# power_board.net
KiCad netlist of a schematic drawn in EAGLE
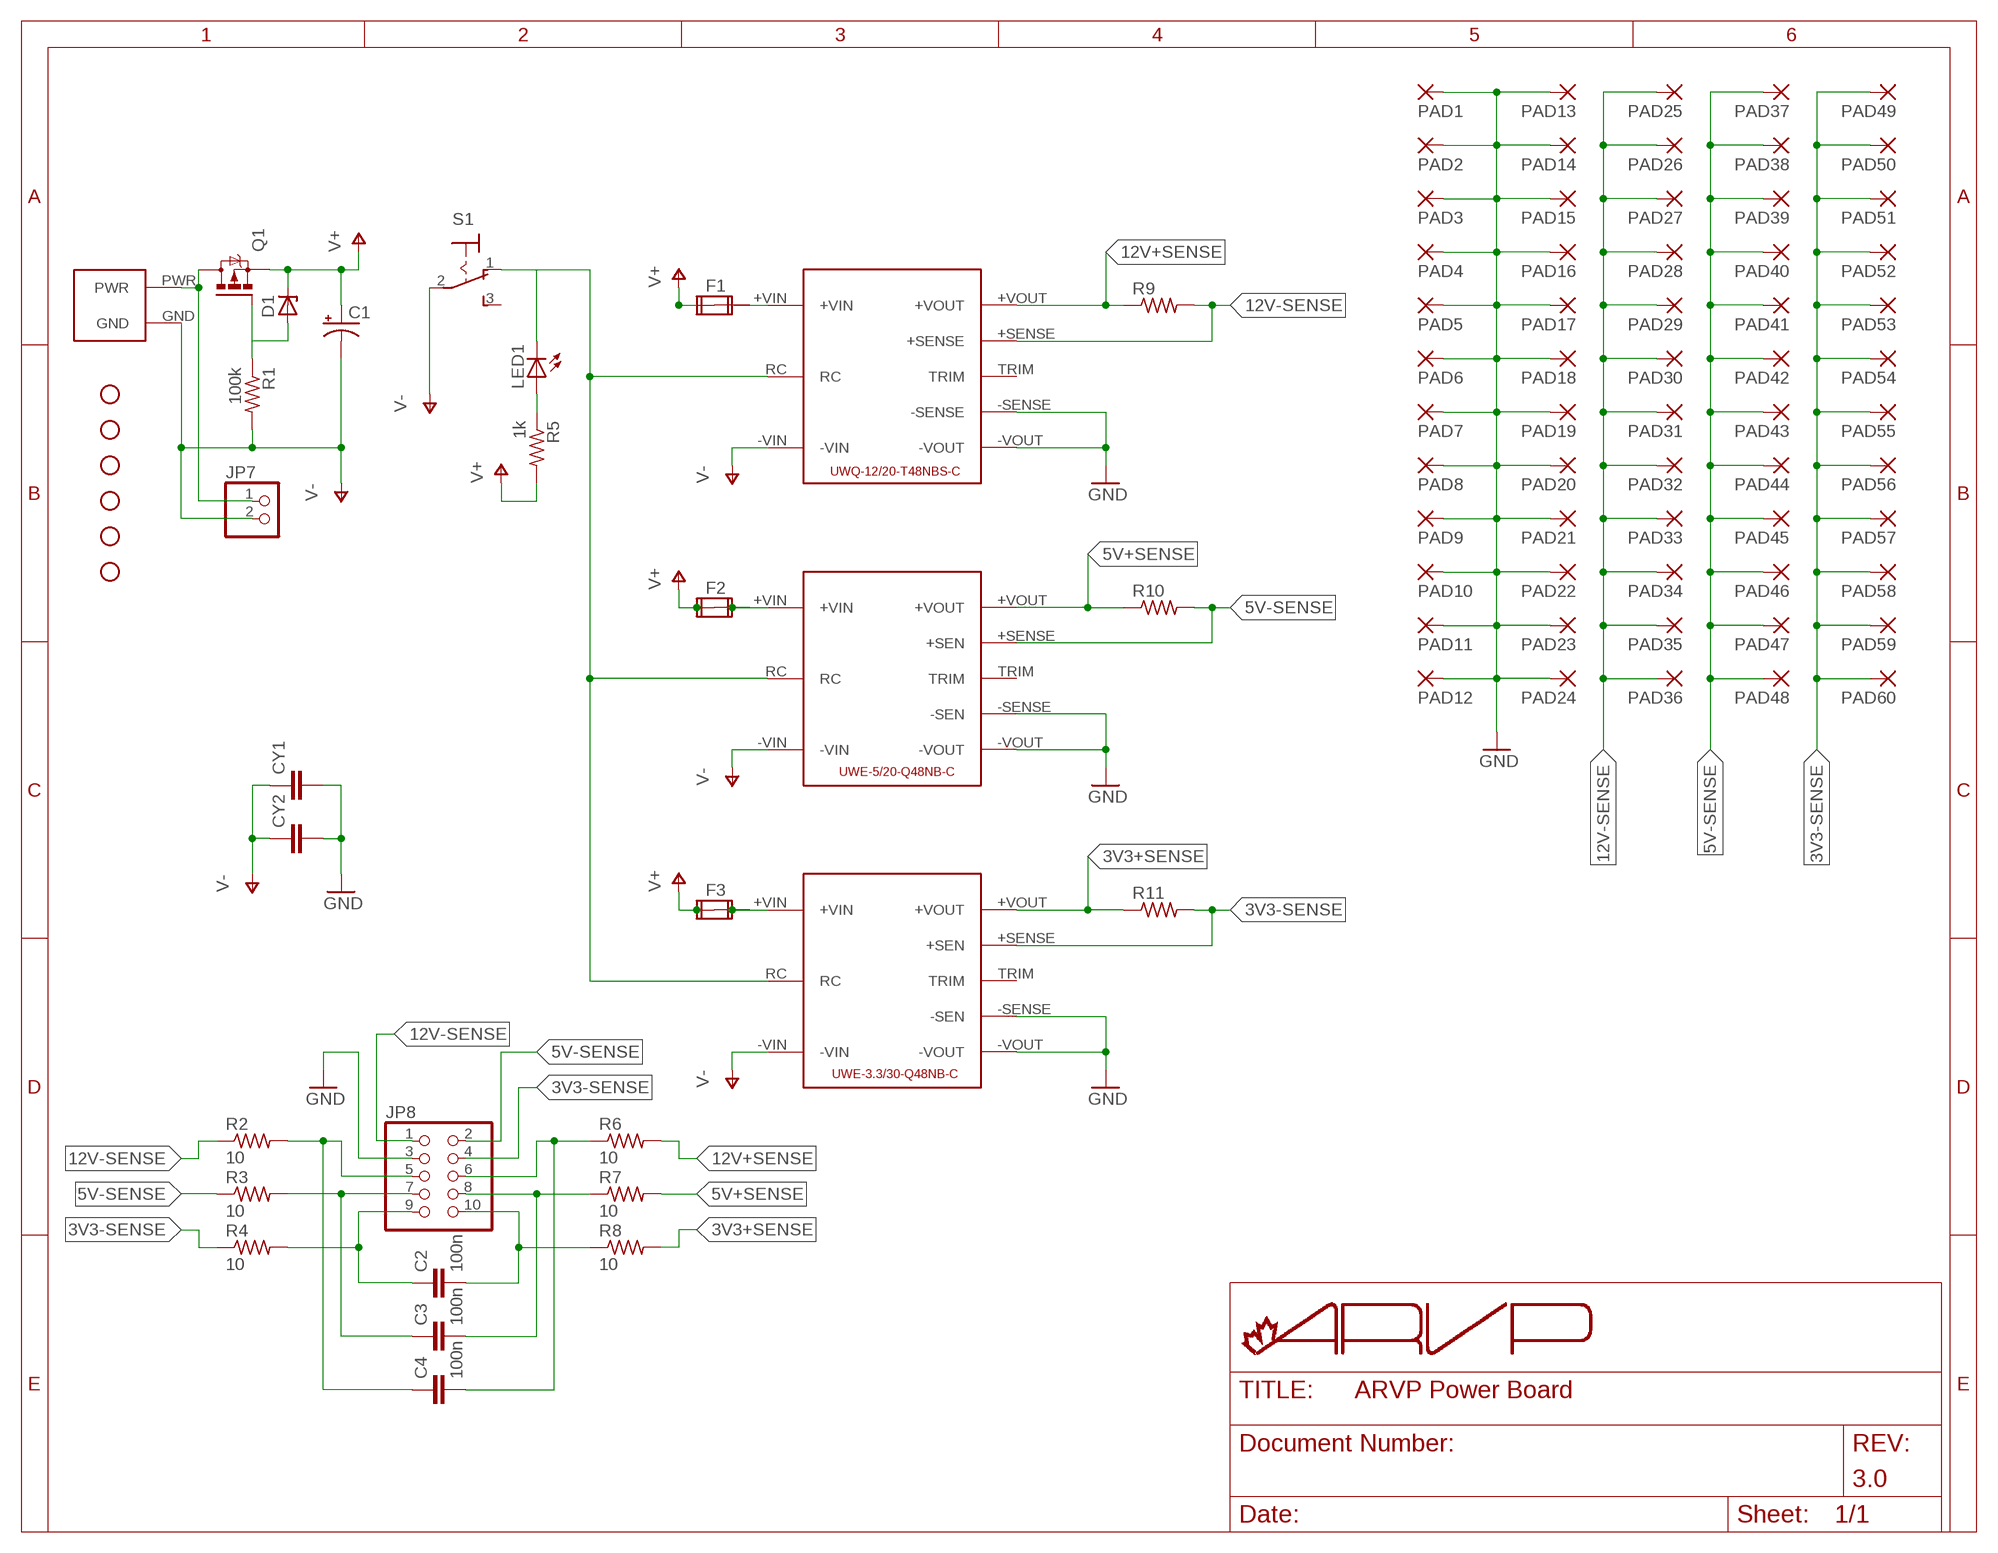
[diagram p0: schematic, sheet 1]

(export (version "E")
  (design (tool "Eeschema 10.0.6"))
  (components
    (comp (ref "C1")
      (value "CPOL-USE5-10.5")
      (footprint "eagle-import:E5-10,5")
      (libsource (lib "eagle-import") (part "CPOL-USE5-10.5"))
    )
    (comp (ref "C2")
      (value "100n")
      (footprint "eagle-import:C025-024X044")
      (libsource (lib "eagle-import") (part "C-EU025-024X044"))
    )
    (comp (ref "C3")
      (value "100n")
      (footprint "eagle-import:C025-024X044")
      (libsource (lib "eagle-import") (part "C-EU025-024X044"))
    )
    (comp (ref "C4")
      (value "100n")
      (footprint "eagle-import:C025-024X044")
      (libsource (lib "eagle-import") (part "C-EU025-024X044"))
    )
    (comp (ref "CY1")
      (value "CYYC7B5")
      (footprint "eagle-import:YC7B5")
      (libsource (lib "eagle-import") (part "CYYC7B5"))
    )
    (comp (ref "CY2")
      (value "CYYC7B5")
      (footprint "eagle-import:YC7B5")
      (libsource (lib "eagle-import") (part "CYYC7B5"))
    )
    (comp (ref "D1")
      (value "ZENER-DIODEDO35Z10")
      (footprint "eagle-import:DO35Z10")
      (libsource (lib "eagle-import") (part "ZENER-DIODEDO35Z10"))
    )
    (comp (ref "F1")
      (value "FUSE2P")
      (footprint "eagle-import:FUSE1")
      (libsource (lib "eagle-import") (part "FUSE2P"))
    )
    (comp (ref "F2")
      (value "FUSE2P")
      (footprint "eagle-import:FUSE1")
      (libsource (lib "eagle-import") (part "FUSE2P"))
    )
    (comp (ref "F3")
      (value "FUSE2P")
      (footprint "eagle-import:FUSE1")
      (libsource (lib "eagle-import") (part "FUSE2P"))
    )
    (comp (ref "JP1")
      (value "STAND-OFF")
      (footprint "eagle-import:STAND-OFF")
      (libsource (lib "eagle-import") (part "STAND-OFF"))
    )
    (comp (ref "JP2")
      (value "STAND-OFF")
      (footprint "eagle-import:STAND-OFF")
      (libsource (lib "eagle-import") (part "STAND-OFF"))
    )
    (comp (ref "JP3")
      (value "STAND-OFF")
      (footprint "eagle-import:STAND-OFF")
      (libsource (lib "eagle-import") (part "STAND-OFF"))
    )
    (comp (ref "JP4")
      (value "STAND-OFF")
      (footprint "eagle-import:STAND-OFF")
      (libsource (lib "eagle-import") (part "STAND-OFF"))
    )
    (comp (ref "JP5")
      (value "STAND-OFF")
      (footprint "eagle-import:STAND-OFF")
      (libsource (lib "eagle-import") (part "STAND-OFF"))
    )
    (comp (ref "JP6")
      (value "STAND-OFF")
      (footprint "eagle-import:STAND-OFF")
      (libsource (lib "eagle-import") (part "STAND-OFF"))
    )
    (comp (ref "JP7")
      (value "PINHD-1X2")
      (footprint "eagle-import:1X02")
      (libsource (lib "eagle-import") (part "PINHD-1X2"))
    )
    (comp (ref "JP8")
      (value "PINHD-2X5")
      (footprint "eagle-import:2X05")
      (libsource (lib "eagle-import") (part "PINHD-2X5"))
    )
    (comp (ref "LED1")
      (value "LED3MM")
      (footprint "eagle-import:LED3MM")
      (libsource (lib "eagle-import") (part "LED3MM"))
    )
    (comp (ref "P$1")
      (value "AND_PWR")
      (footprint "eagle-import:AND_PWR")
      (libsource (lib "eagle-import") (part "AND_PWR"))
    )
    (comp (ref "PAD1")
      (value "2,15/1,0")
      (footprint "eagle-import:2,15_1,0")
      (libsource (lib "eagle-import") (part "2,15/1,0"))
    )
    (comp (ref "PAD2")
      (value "2,15/1,0")
      (footprint "eagle-import:2,15_1,0")
      (libsource (lib "eagle-import") (part "2,15/1,0"))
    )
    (comp (ref "PAD3")
      (value "2,15/1,0")
      (footprint "eagle-import:2,15_1,0")
      (libsource (lib "eagle-import") (part "2,15/1,0"))
    )
    (comp (ref "PAD4")
      (value "2,15/1,0")
      (footprint "eagle-import:2,15_1,0")
      (libsource (lib "eagle-import") (part "2,15/1,0"))
    )
    (comp (ref "PAD5")
      (value "2,15/1,0")
      (footprint "eagle-import:2,15_1,0")
      (libsource (lib "eagle-import") (part "2,15/1,0"))
    )
    (comp (ref "PAD6")
      (value "2,15/1,0")
      (footprint "eagle-import:2,15_1,0")
      (libsource (lib "eagle-import") (part "2,15/1,0"))
    )
    (comp (ref "PAD7")
      (value "2,15/1,0")
      (footprint "eagle-import:2,15_1,0")
      (libsource (lib "eagle-import") (part "2,15/1,0"))
    )
    (comp (ref "PAD8")
      (value "2,15/1,0")
      (footprint "eagle-import:2,15_1,0")
      (libsource (lib "eagle-import") (part "2,15/1,0"))
    )
    (comp (ref "PAD9")
      (value "2,15/1,0")
      (footprint "eagle-import:2,15_1,0")
      (libsource (lib "eagle-import") (part "2,15/1,0"))
    )
    (comp (ref "PAD10")
      (value "2,15/1,0")
      (footprint "eagle-import:2,15_1,0")
      (libsource (lib "eagle-import") (part "2,15/1,0"))
    )
    (comp (ref "PAD11")
      (value "2,15/1,0")
      (footprint "eagle-import:2,15_1,0")
      (libsource (lib "eagle-import") (part "2,15/1,0"))
    )
    (comp (ref "PAD12")
      (value "2,15/1,0")
      (footprint "eagle-import:2,15_1,0")
      (libsource (lib "eagle-import") (part "2,15/1,0"))
    )
    (comp (ref "PAD13")
      (value "2,15/1,0")
      (footprint "eagle-import:2,15_1,0")
      (libsource (lib "eagle-import") (part "2,15/1,0"))
    )
    (comp (ref "PAD14")
      (value "2,15/1,0")
      (footprint "eagle-import:2,15_1,0")
      (libsource (lib "eagle-import") (part "2,15/1,0"))
    )
    (comp (ref "PAD15")
      (value "2,15/1,0")
      (footprint "eagle-import:2,15_1,0")
      (libsource (lib "eagle-import") (part "2,15/1,0"))
    )
    (comp (ref "PAD16")
      (value "2,15/1,0")
      (footprint "eagle-import:2,15_1,0")
      (libsource (lib "eagle-import") (part "2,15/1,0"))
    )
    (comp (ref "PAD17")
      (value "2,15/1,0")
      (footprint "eagle-import:2,15_1,0")
      (libsource (lib "eagle-import") (part "2,15/1,0"))
    )
    (comp (ref "PAD18")
      (value "2,15/1,0")
      (footprint "eagle-import:2,15_1,0")
      (libsource (lib "eagle-import") (part "2,15/1,0"))
    )
    (comp (ref "PAD19")
      (value "2,15/1,0")
      (footprint "eagle-import:2,15_1,0")
      (libsource (lib "eagle-import") (part "2,15/1,0"))
    )
    (comp (ref "PAD20")
      (value "2,15/1,0")
      (footprint "eagle-import:2,15_1,0")
      (libsource (lib "eagle-import") (part "2,15/1,0"))
    )
    (comp (ref "PAD21")
      (value "2,15/1,0")
      (footprint "eagle-import:2,15_1,0")
      (libsource (lib "eagle-import") (part "2,15/1,0"))
    )
    (comp (ref "PAD22")
      (value "2,15/1,0")
      (footprint "eagle-import:2,15_1,0")
      (libsource (lib "eagle-import") (part "2,15/1,0"))
    )
    (comp (ref "PAD23")
      (value "2,15/1,0")
      (footprint "eagle-import:2,15_1,0")
      (libsource (lib "eagle-import") (part "2,15/1,0"))
    )
    (comp (ref "PAD24")
      (value "2,15/1,0")
      (footprint "eagle-import:2,15_1,0")
      (libsource (lib "eagle-import") (part "2,15/1,0"))
    )
    (comp (ref "PAD25")
      (value "2,15/1,0")
      (footprint "eagle-import:2,15_1,0")
      (libsource (lib "eagle-import") (part "2,15/1,0"))
    )
    (comp (ref "PAD26")
      (value "2,15/1,0")
      (footprint "eagle-import:2,15_1,0")
      (libsource (lib "eagle-import") (part "2,15/1,0"))
    )
    (comp (ref "PAD27")
      (value "2,15/1,0")
      (footprint "eagle-import:2,15_1,0")
      (libsource (lib "eagle-import") (part "2,15/1,0"))
    )
    (comp (ref "PAD28")
      (value "2,15/1,0")
      (footprint "eagle-import:2,15_1,0")
      (libsource (lib "eagle-import") (part "2,15/1,0"))
    )
    (comp (ref "PAD29")
      (value "2,15/1,0")
      (footprint "eagle-import:2,15_1,0")
      (libsource (lib "eagle-import") (part "2,15/1,0"))
    )
    (comp (ref "PAD30")
      (value "2,15/1,0")
      (footprint "eagle-import:2,15_1,0")
      (libsource (lib "eagle-import") (part "2,15/1,0"))
    )
    (comp (ref "PAD31")
      (value "2,15/1,0")
      (footprint "eagle-import:2,15_1,0")
      (libsource (lib "eagle-import") (part "2,15/1,0"))
    )
    (comp (ref "PAD32")
      (value "2,15/1,0")
      (footprint "eagle-import:2,15_1,0")
      (libsource (lib "eagle-import") (part "2,15/1,0"))
    )
    (comp (ref "PAD33")
      (value "2,15/1,0")
      (footprint "eagle-import:2,15_1,0")
      (libsource (lib "eagle-import") (part "2,15/1,0"))
    )
    (comp (ref "PAD34")
      (value "2,15/1,0")
      (footprint "eagle-import:2,15_1,0")
      (libsource (lib "eagle-import") (part "2,15/1,0"))
    )
    (comp (ref "PAD35")
      (value "2,15/1,0")
      (footprint "eagle-import:2,15_1,0")
      (libsource (lib "eagle-import") (part "2,15/1,0"))
    )
    (comp (ref "PAD36")
      (value "2,15/1,0")
      (footprint "eagle-import:2,15_1,0")
      (libsource (lib "eagle-import") (part "2,15/1,0"))
    )
    (comp (ref "PAD37")
      (value "2,15/1,0")
      (footprint "eagle-import:2,15_1,0")
      (libsource (lib "eagle-import") (part "2,15/1,0"))
    )
    (comp (ref "PAD38")
      (value "2,15/1,0")
      (footprint "eagle-import:2,15_1,0")
      (libsource (lib "eagle-import") (part "2,15/1,0"))
    )
    (comp (ref "PAD39")
      (value "2,15/1,0")
      (footprint "eagle-import:2,15_1,0")
      (libsource (lib "eagle-import") (part "2,15/1,0"))
    )
    (comp (ref "PAD40")
      (value "2,15/1,0")
      (footprint "eagle-import:2,15_1,0")
      (libsource (lib "eagle-import") (part "2,15/1,0"))
    )
    (comp (ref "PAD41")
      (value "2,15/1,0")
      (footprint "eagle-import:2,15_1,0")
      (libsource (lib "eagle-import") (part "2,15/1,0"))
    )
    (comp (ref "PAD42")
      (value "2,15/1,0")
      (footprint "eagle-import:2,15_1,0")
      (libsource (lib "eagle-import") (part "2,15/1,0"))
    )
    (comp (ref "PAD43")
      (value "2,15/1,0")
      (footprint "eagle-import:2,15_1,0")
      (libsource (lib "eagle-import") (part "2,15/1,0"))
    )
    (comp (ref "PAD44")
      (value "2,15/1,0")
      (footprint "eagle-import:2,15_1,0")
      (libsource (lib "eagle-import") (part "2,15/1,0"))
    )
    (comp (ref "PAD45")
      (value "2,15/1,0")
      (footprint "eagle-import:2,15_1,0")
      (libsource (lib "eagle-import") (part "2,15/1,0"))
    )
    (comp (ref "PAD46")
      (value "2,15/1,0")
      (footprint "eagle-import:2,15_1,0")
      (libsource (lib "eagle-import") (part "2,15/1,0"))
    )
    (comp (ref "PAD47")
      (value "2,15/1,0")
      (footprint "eagle-import:2,15_1,0")
      (libsource (lib "eagle-import") (part "2,15/1,0"))
    )
    (comp (ref "PAD48")
      (value "2,15/1,0")
      (footprint "eagle-import:2,15_1,0")
      (libsource (lib "eagle-import") (part "2,15/1,0"))
    )
    (comp (ref "PAD49")
      (value "2,15/1,0")
      (footprint "eagle-import:2,15_1,0")
      (libsource (lib "eagle-import") (part "2,15/1,0"))
    )
    (comp (ref "PAD50")
      (value "2,15/1,0")
      (footprint "eagle-import:2,15_1,0")
      (libsource (lib "eagle-import") (part "2,15/1,0"))
    )
    (comp (ref "PAD51")
      (value "2,15/1,0")
      (footprint "eagle-import:2,15_1,0")
      (libsource (lib "eagle-import") (part "2,15/1,0"))
    )
    (comp (ref "PAD52")
      (value "2,15/1,0")
      (footprint "eagle-import:2,15_1,0")
      (libsource (lib "eagle-import") (part "2,15/1,0"))
    )
    (comp (ref "PAD53")
      (value "2,15/1,0")
      (footprint "eagle-import:2,15_1,0")
      (libsource (lib "eagle-import") (part "2,15/1,0"))
    )
    (comp (ref "PAD54")
      (value "2,15/1,0")
      (footprint "eagle-import:2,15_1,0")
      (libsource (lib "eagle-import") (part "2,15/1,0"))
    )
    (comp (ref "PAD55")
      (value "2,15/1,0")
      (footprint "eagle-import:2,15_1,0")
      (libsource (lib "eagle-import") (part "2,15/1,0"))
    )
    (comp (ref "PAD56")
      (value "2,15/1,0")
      (footprint "eagle-import:2,15_1,0")
      (libsource (lib "eagle-import") (part "2,15/1,0"))
    )
    (comp (ref "PAD57")
      (value "2,15/1,0")
      (footprint "eagle-import:2,15_1,0")
      (libsource (lib "eagle-import") (part "2,15/1,0"))
    )
    (comp (ref "PAD58")
      (value "2,15/1,0")
      (footprint "eagle-import:2,15_1,0")
      (libsource (lib "eagle-import") (part "2,15/1,0"))
    )
    (comp (ref "PAD59")
      (value "2,15/1,0")
      (footprint "eagle-import:2,15_1,0")
      (libsource (lib "eagle-import") (part "2,15/1,0"))
    )
    (comp (ref "PAD60")
      (value "2,15/1,0")
      (footprint "eagle-import:2,15_1,0")
      (libsource (lib "eagle-import") (part "2,15/1,0"))
    )
    (comp (ref "Q1")
      (value "IPP80P03P4L04AKSA1")
      (footprint "eagle-import:TO220BV")
      (libsource (lib "eagle-import") (part "IPP80P03P4L04AKSA1"))
    )
    (comp (ref "R1")
      (value "100k")
      (footprint "eagle-import:0204_7")
      (libsource (lib "eagle-import") (part "resistor_R-US_0204/7"))
    )
    (comp (ref "R2")
      (value "10")
      (footprint "eagle-import:0204_5")
      (libsource (lib "eagle-import") (part "R-US_0204/5"))
    )
    (comp (ref "R3")
      (value "10")
      (footprint "eagle-import:0204_5")
      (libsource (lib "eagle-import") (part "R-US_0204/5"))
    )
    (comp (ref "R4")
      (value "10")
      (footprint "eagle-import:0204_5")
      (libsource (lib "eagle-import") (part "R-US_0204/5"))
    )
    (comp (ref "R5")
      (value "1k")
      (footprint "eagle-import:0204_7")
      (libsource (lib "eagle-import") (part "resistor_R-US_0204/7"))
    )
    (comp (ref "R6")
      (value "10")
      (footprint "eagle-import:0204_5")
      (libsource (lib "eagle-import") (part "R-US_0204/5"))
    )
    (comp (ref "R7")
      (value "10")
      (footprint "eagle-import:0204_5")
      (libsource (lib "eagle-import") (part "R-US_0204/5"))
    )
    (comp (ref "R8")
      (value "10")
      (footprint "eagle-import:0204_5")
      (libsource (lib "eagle-import") (part "R-US_0204/5"))
    )
    (comp (ref "R9")
      (value "R-US_0617/22")
      (footprint "eagle-import:0617_22")
      (libsource (lib "eagle-import") (part "R-US_0617/22"))
    )
    (comp (ref "R10")
      (value "R-US_0617/22")
      (footprint "eagle-import:0617_22")
      (libsource (lib "eagle-import") (part "R-US_0617/22"))
    )
    (comp (ref "R11")
      (value "R-US_0617/22")
      (footprint "eagle-import:0617_22")
      (libsource (lib "eagle-import") (part "R-US_0617/22"))
    )
    (comp (ref "S1")
      (value "M9040P")
      (footprint "eagle-import:M9040P")
      (libsource (lib "eagle-import") (part "M9040P"))
    )
    (comp (ref "U1")
      (value "UWQ-12/20-T48NBS-C")
      (footprint "eagle-import:UWQ-12_20-T48")
      (libsource (lib "eagle-import") (part "UWQ-12/20-T48NBS-C"))
    )
    (comp (ref "U2")
      (value "UWE-5/20-Q48NB-C")
      (footprint "eagle-import:UWE-100-120W")
      (libsource (lib "eagle-import") (part "UWE-5/20-Q48NB-C"))
    )
    (comp (ref "U3")
      (value "UWE-3.3/30-Q48NB-C")
      (footprint "eagle-import:UWE-100-120W")
      (libsource (lib "eagle-import") (part "UWE-3.3/30-Q48NB-C"))
    )
  )
  (nets
    (net (code "1") (name "3V3+SENSE") (class "Default")
      (node (ref "R11") (pin "1") (pinfunction "1_1") (pintype "passive"))
      (node (ref "R8") (pin "2") (pinfunction "2_2") (pintype "passive"))
      (node (ref "U3") (pin "+VOUT") (pinfunction "+VOUT_+VOUT") (pintype "power_in"))
    )
    (net (code "2") (name "3V3-SENSE") (class "Default")
      (node (ref "JP8") (pin "4") (pinfunction "4_4") (pintype "passive"))
      (node (ref "PAD49") (pin "1") (pinfunction "P_1") (pintype "passive"))
      (node (ref "PAD50") (pin "1") (pinfunction "P_1") (pintype "passive"))
      (node (ref "PAD51") (pin "1") (pinfunction "P_1") (pintype "passive"))
      (node (ref "PAD52") (pin "1") (pinfunction "P_1") (pintype "passive"))
      (node (ref "PAD53") (pin "1") (pinfunction "P_1") (pintype "passive"))
      (node (ref "PAD54") (pin "1") (pinfunction "P_1") (pintype "passive"))
      (node (ref "PAD55") (pin "1") (pinfunction "P_1") (pintype "passive"))
      (node (ref "PAD56") (pin "1") (pinfunction "P_1") (pintype "passive"))
      (node (ref "PAD57") (pin "1") (pinfunction "P_1") (pintype "passive"))
      (node (ref "PAD58") (pin "1") (pinfunction "P_1") (pintype "passive"))
      (node (ref "PAD59") (pin "1") (pinfunction "P_1") (pintype "passive"))
      (node (ref "PAD60") (pin "1") (pinfunction "P_1") (pintype "passive"))
      (node (ref "R11") (pin "2") (pinfunction "2_2") (pintype "passive"))
      (node (ref "R4") (pin "1") (pinfunction "1_1") (pintype "passive"))
      (node (ref "U3") (pin "+SENSE") (pinfunction "+SEN_+SENSE") (pintype "bidirectional"))
    )
    (net (code "3") (name "5V+SENSE") (class "Default")
      (node (ref "R10") (pin "1") (pinfunction "1_1") (pintype "passive"))
      (node (ref "R7") (pin "2") (pinfunction "2_2") (pintype "passive"))
      (node (ref "U2") (pin "+VOUT") (pinfunction "+VOUT_+VOUT") (pintype "power_in"))
    )
    (net (code "4") (name "5V-SENSE") (class "Default")
      (node (ref "JP8") (pin "2") (pinfunction "2_2") (pintype "passive"))
      (node (ref "PAD37") (pin "1") (pinfunction "P_1") (pintype "passive"))
      (node (ref "PAD38") (pin "1") (pinfunction "P_1") (pintype "passive"))
      (node (ref "PAD39") (pin "1") (pinfunction "P_1") (pintype "passive"))
      (node (ref "PAD40") (pin "1") (pinfunction "P_1") (pintype "passive"))
      (node (ref "PAD41") (pin "1") (pinfunction "P_1") (pintype "passive"))
      (node (ref "PAD42") (pin "1") (pinfunction "P_1") (pintype "passive"))
      (node (ref "PAD43") (pin "1") (pinfunction "P_1") (pintype "passive"))
      (node (ref "PAD44") (pin "1") (pinfunction "P_1") (pintype "passive"))
      (node (ref "PAD45") (pin "1") (pinfunction "P_1") (pintype "passive"))
      (node (ref "PAD46") (pin "1") (pinfunction "P_1") (pintype "passive"))
      (node (ref "PAD47") (pin "1") (pinfunction "P_1") (pintype "passive"))
      (node (ref "PAD48") (pin "1") (pinfunction "P_1") (pintype "passive"))
      (node (ref "R10") (pin "2") (pinfunction "2_2") (pintype "passive"))
      (node (ref "R3") (pin "1") (pinfunction "1_1") (pintype "passive"))
      (node (ref "U2") (pin "+SENSE") (pinfunction "+SEN_+SENSE") (pintype "bidirectional"))
    )
    (net (code "5") (name "12V+SENSE") (class "Default")
      (node (ref "R6") (pin "2") (pinfunction "2_2") (pintype "passive"))
      (node (ref "R9") (pin "1") (pinfunction "1_1") (pintype "passive"))
      (node (ref "U1") (pin "+VOUT") (pinfunction "+VOUT_+VOUT") (pintype "power_in"))
    )
    (net (code "6") (name "12V-SENSE") (class "Default")
      (node (ref "JP8") (pin "1") (pinfunction "1_1") (pintype "passive"))
      (node (ref "PAD25") (pin "1") (pinfunction "P_1") (pintype "passive"))
      (node (ref "PAD26") (pin "1") (pinfunction "P_1") (pintype "passive"))
      (node (ref "PAD27") (pin "1") (pinfunction "P_1") (pintype "passive"))
      (node (ref "PAD28") (pin "1") (pinfunction "P_1") (pintype "passive"))
      (node (ref "PAD29") (pin "1") (pinfunction "P_1") (pintype "passive"))
      (node (ref "PAD30") (pin "1") (pinfunction "P_1") (pintype "passive"))
      (node (ref "PAD31") (pin "1") (pinfunction "P_1") (pintype "passive"))
      (node (ref "PAD32") (pin "1") (pinfunction "P_1") (pintype "passive"))
      (node (ref "PAD33") (pin "1") (pinfunction "P_1") (pintype "passive"))
      (node (ref "PAD34") (pin "1") (pinfunction "P_1") (pintype "passive"))
      (node (ref "PAD35") (pin "1") (pinfunction "P_1") (pintype "passive"))
      (node (ref "PAD36") (pin "1") (pinfunction "P_1") (pintype "passive"))
      (node (ref "R2") (pin "1") (pinfunction "1_1") (pintype "passive"))
      (node (ref "R9") (pin "2") (pinfunction "2_2") (pintype "passive"))
      (node (ref "U1") (pin "+SENSE") (pinfunction "+SENSE_+SENSE") (pintype "bidirectional"))
    )
    (net (code "7") (name "GND") (class "Default")
      (node (ref "CY1") (pin "2") (pinfunction "2_2") (pintype "passive"))
      (node (ref "CY2") (pin "2") (pinfunction "2_2") (pintype "passive"))
      (node (ref "JP8") (pin "3") (pinfunction "3_3") (pintype "passive"))
      (node (ref "PAD1") (pin "1") (pinfunction "P_1") (pintype "passive"))
      (node (ref "PAD10") (pin "1") (pinfunction "P_1") (pintype "passive"))
      (node (ref "PAD11") (pin "1") (pinfunction "P_1") (pintype "passive"))
      (node (ref "PAD12") (pin "1") (pinfunction "P_1") (pintype "passive"))
      (node (ref "PAD13") (pin "1") (pinfunction "P_1") (pintype "passive"))
      (node (ref "PAD14") (pin "1") (pinfunction "P_1") (pintype "passive"))
      (node (ref "PAD15") (pin "1") (pinfunction "P_1") (pintype "passive"))
      (node (ref "PAD16") (pin "1") (pinfunction "P_1") (pintype "passive"))
      (node (ref "PAD17") (pin "1") (pinfunction "P_1") (pintype "passive"))
      (node (ref "PAD18") (pin "1") (pinfunction "P_1") (pintype "passive"))
      (node (ref "PAD19") (pin "1") (pinfunction "P_1") (pintype "passive"))
      (node (ref "PAD2") (pin "1") (pinfunction "P_1") (pintype "passive"))
      (node (ref "PAD20") (pin "1") (pinfunction "P_1") (pintype "passive"))
      (node (ref "PAD21") (pin "1") (pinfunction "P_1") (pintype "passive"))
      (node (ref "PAD22") (pin "1") (pinfunction "P_1") (pintype "passive"))
      (node (ref "PAD23") (pin "1") (pinfunction "P_1") (pintype "passive"))
      (node (ref "PAD24") (pin "1") (pinfunction "P_1") (pintype "passive"))
      (node (ref "PAD3") (pin "1") (pinfunction "P_1") (pintype "passive"))
      (node (ref "PAD4") (pin "1") (pinfunction "P_1") (pintype "passive"))
      (node (ref "PAD5") (pin "1") (pinfunction "P_1") (pintype "passive"))
      (node (ref "PAD6") (pin "1") (pinfunction "P_1") (pintype "passive"))
      (node (ref "PAD7") (pin "1") (pinfunction "P_1") (pintype "passive"))
      (node (ref "PAD8") (pin "1") (pinfunction "P_1") (pintype "passive"))
      (node (ref "PAD9") (pin "1") (pinfunction "P_1") (pintype "passive"))
      (node (ref "U1") (pin "-SENSE") (pinfunction "-SENSE_-SENSE") (pintype "bidirectional"))
      (node (ref "U1") (pin "-VOUT") (pinfunction "-VOUT_-VOUT") (pintype "power_in"))
      (node (ref "U2") (pin "-SENSE") (pinfunction "-SEN_-SENSE") (pintype "bidirectional"))
      (node (ref "U2") (pin "-VOUT") (pinfunction "-VOUT_-VOUT") (pintype "power_in"))
      (node (ref "U3") (pin "-SENSE") (pinfunction "-SEN_-SENSE") (pintype "bidirectional"))
      (node (ref "U3") (pin "-VOUT") (pinfunction "-VOUT_-VOUT") (pintype "power_in"))
    )
    (net (code "8") (name "Net-(C2-Pad1)") (class "Default")
      (node (ref "C2") (pin "1") (pinfunction "1_1") (pintype "passive"))
      (node (ref "JP8") (pin "9") (pinfunction "9_9") (pintype "passive"))
      (node (ref "R4") (pin "2") (pinfunction "2_2") (pintype "passive"))
    )
    (net (code "9") (name "Net-(C2-Pad2)") (class "Default")
      (node (ref "C2") (pin "2") (pinfunction "2_2") (pintype "passive"))
      (node (ref "JP8") (pin "10") (pinfunction "10_10") (pintype "passive"))
      (node (ref "R8") (pin "1") (pinfunction "1_1") (pintype "passive"))
    )
    (net (code "10") (name "Net-(C3-Pad1)") (class "Default")
      (node (ref "C3") (pin "1") (pinfunction "1_1") (pintype "passive"))
      (node (ref "JP8") (pin "7") (pinfunction "7_7") (pintype "passive"))
      (node (ref "R3") (pin "2") (pinfunction "2_2") (pintype "passive"))
    )
    (net (code "11") (name "Net-(C3-Pad2)") (class "Default")
      (node (ref "C3") (pin "2") (pinfunction "2_2") (pintype "passive"))
      (node (ref "JP8") (pin "8") (pinfunction "8_8") (pintype "passive"))
      (node (ref "R7") (pin "1") (pinfunction "1_1") (pintype "passive"))
    )
    (net (code "12") (name "Net-(C4-Pad1)") (class "Default")
      (node (ref "C4") (pin "1") (pinfunction "1_1") (pintype "passive"))
      (node (ref "JP8") (pin "5") (pinfunction "5_5") (pintype "passive"))
      (node (ref "R2") (pin "2") (pinfunction "2_2") (pintype "passive"))
    )
    (net (code "13") (name "Net-(C4-Pad2)") (class "Default")
      (node (ref "C4") (pin "2") (pinfunction "2_2") (pintype "passive"))
      (node (ref "JP8") (pin "6") (pinfunction "6_6") (pintype "passive"))
      (node (ref "R6") (pin "1") (pinfunction "1_1") (pintype "passive"))
    )
    (net (code "14") (name "Net-(D1-PadA)") (class "Default")
      (node (ref "D1") (pin "A") (pinfunction "A_A") (pintype "passive"))
      (node (ref "Q1") (pin "G") (pinfunction "G_G") (pintype "power_in"))
      (node (ref "R1") (pin "1") (pinfunction "1_1") (pintype "passive"))
    )
    (net (code "15") (name "Net-(F1-Pad2A)") (class "Default")
      (node (ref "F1") (pin "2A") (pinfunction "2A_2A") (pintype "passive"))
      (node (ref "F1") (pin "2B") (pinfunction "2B_2B") (pintype "passive"))
      (node (ref "U1") (pin "+VIN") (pinfunction "+VIN_+VIN") (pintype "power_in"))
    )
    (net (code "16") (name "Net-(F2-Pad2A)") (class "Default")
      (node (ref "F2") (pin "2A") (pinfunction "2A_2A") (pintype "passive"))
      (node (ref "F2") (pin "2B") (pinfunction "2B_2B") (pintype "passive"))
      (node (ref "U2") (pin "+VIN") (pinfunction "+VIN_+VIN") (pintype "power_in"))
    )
    (net (code "17") (name "Net-(F3-Pad2A)") (class "Default")
      (node (ref "F3") (pin "2A") (pinfunction "2A_2A") (pintype "passive"))
      (node (ref "F3") (pin "2B") (pinfunction "2B_2B") (pintype "passive"))
      (node (ref "U3") (pin "+VIN") (pinfunction "+VIN_+VIN") (pintype "power_in"))
    )
    (net (code "18") (name "Net-(JP7-Pad1)") (class "Default")
      (node (ref "JP7") (pin "1") (pinfunction "1_1") (pintype "passive"))
      (node (ref "P$1") (pin "PWR") (pinfunction "PWR_PWR") (pintype "bidirectional"))
      (node (ref "Q1") (pin "D") (pinfunction "D_D") (pintype "power_in"))
    )
    (net (code "19") (name "Net-(LED1-C)") (class "Default")
      (node (ref "LED1") (pin "K") (pinfunction "C_K") (pintype "passive"))
      (node (ref "S1") (pin "1") (pinfunction "O_1") (pintype "passive"))
      (node (ref "U1") (pin "RC") (pinfunction "RC_RC") (pintype "bidirectional"))
      (node (ref "U2") (pin "RC") (pinfunction "RC_RC") (pintype "bidirectional"))
      (node (ref "U3") (pin "RC") (pinfunction "RC_RC") (pintype "bidirectional"))
    )
    (net (code "20") (name "Net-(LED1-PadA)") (class "Default")
      (node (ref "LED1") (pin "A") (pinfunction "A_A") (pintype "passive"))
      (node (ref "R5") (pin "1") (pinfunction "1_1") (pintype "passive"))
    )
    (net (code "21") (name "V+") (class "Default")
      (node (ref "C1") (pin "+") (pinfunction "+_+") (pintype "passive"))
      (node (ref "D1") (pin "C") (pinfunction "C_C") (pintype "passive"))
      (node (ref "F1") (pin "1A") (pinfunction "1A_1A") (pintype "passive"))
      (node (ref "F1") (pin "1B") (pinfunction "1B_1B") (pintype "passive"))
      (node (ref "F2") (pin "1A") (pinfunction "1A_1A") (pintype "passive"))
      (node (ref "F2") (pin "1B") (pinfunction "1B_1B") (pintype "passive"))
      (node (ref "F3") (pin "1A") (pinfunction "1A_1A") (pintype "passive"))
      (node (ref "F3") (pin "1B") (pinfunction "1B_1B") (pintype "passive"))
      (node (ref "Q1") (pin "S") (pinfunction "S_S") (pintype "power_in"))
      (node (ref "R5") (pin "2") (pinfunction "2_2") (pintype "passive"))
    )
    (net (code "22") (name "V-") (class "Default")
      (node (ref "C1") (pin "-") (pinfunction "-_-") (pintype "passive"))
      (node (ref "CY1") (pin "1") (pinfunction "1_1") (pintype "passive"))
      (node (ref "CY2") (pin "1") (pinfunction "1_1") (pintype "passive"))
      (node (ref "JP7") (pin "2") (pinfunction "2_2") (pintype "passive"))
      (node (ref "P$1") (pin "GND") (pinfunction "GND_GND") (pintype "bidirectional"))
      (node (ref "R1") (pin "2") (pinfunction "2_2") (pintype "passive"))
      (node (ref "S1") (pin "2") (pinfunction "P_2") (pintype "passive"))
      (node (ref "U1") (pin "-VIN") (pinfunction "-VIN_-VIN") (pintype "power_in"))
      (node (ref "U2") (pin "-VIN") (pinfunction "-VIN_-VIN") (pintype "power_in"))
      (node (ref "U3") (pin "-VIN") (pinfunction "-VIN_-VIN") (pintype "power_in"))
    )
    (net (code "23") (name "unconnected-(S1-S-Pad3)") (class "Default")
      (node (ref "S1") (pin "3") (pinfunction "S_3") (pintype "passive"))
    )
    (net (code "24") (name "unconnected-(U1-PadTRIM)") (class "Default")
      (node (ref "U1") (pin "TRIM") (pinfunction "TRIM_TRIM") (pintype "bidirectional"))
    )
    (net (code "25") (name "unconnected-(U2-PadTRIM)") (class "Default")
      (node (ref "U2") (pin "TRIM") (pinfunction "TRIM_TRIM") (pintype "bidirectional"))
    )
    (net (code "26") (name "unconnected-(U3-PadTRIM)") (class "Default")
      (node (ref "U3") (pin "TRIM") (pinfunction "TRIM_TRIM") (pintype "bidirectional"))
    )
  )
)
